# GNSS_RECV.net
KiCad netlist of a schematic drawn in Altium Designer
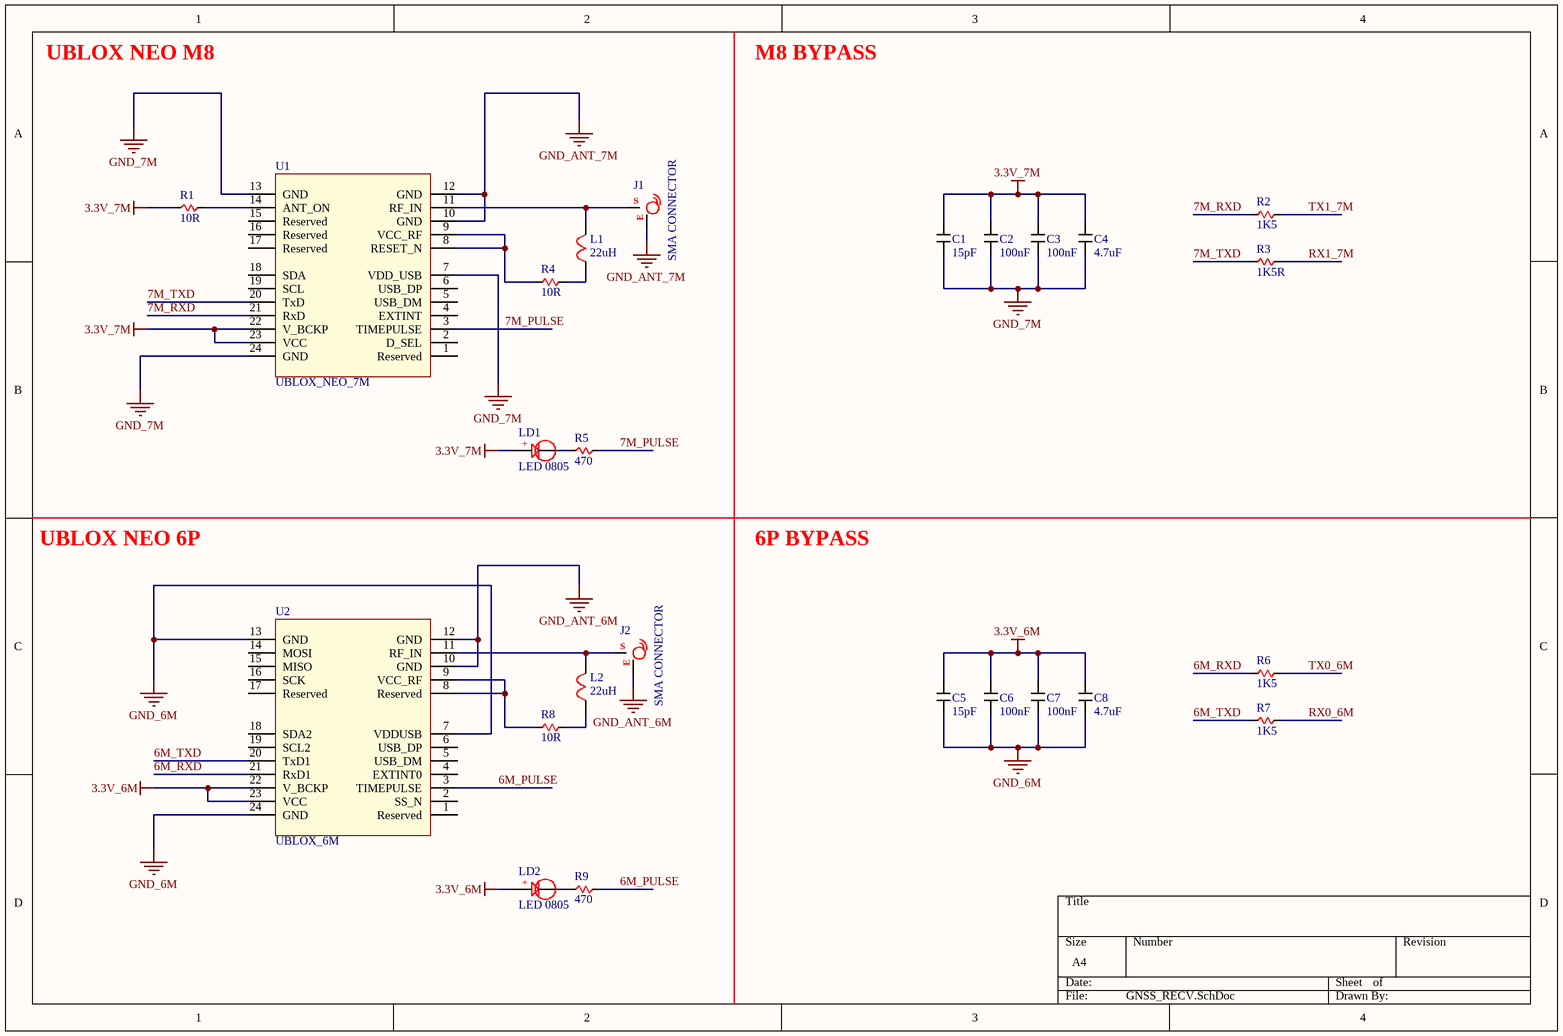
[diagram p0: GNSS_RECV.SchDoc]

(export (version "E")
  (design (tool "Eeschema 10.0.6"))
  (components
    (comp (ref "C1") (value "15pF") (footprint "C 0805") (libsource (lib "SkyWar") (part "C 0805")))
    (comp (ref "C2") (value "100nF") (footprint "C 0805") (libsource (lib "SkyWar") (part "C 0805")))
    (comp (ref "C3") (value "100nF") (footprint "C 0805") (libsource (lib "SkyWar") (part "C 0805")))
    (comp (ref "C4") (value "4.7uF") (footprint "C 0805") (libsource (lib "SkyWar") (part "C 0805")))
    (comp (ref "C5") (value "15pF") (footprint "C 0805") (libsource (lib "SkyWar") (part "C 0805")))
    (comp (ref "C6") (value "100nF") (footprint "C 0805") (libsource (lib "SkyWar") (part "C 0805")))
    (comp (ref "C7") (value "100nF") (footprint "C 0805") (libsource (lib "SkyWar") (part "C 0805")))
    (comp (ref "C8") (value "4.7uF") (footprint "C 0805") (libsource (lib "SkyWar") (part "C 0805")))
    (comp (ref "J1")
      (value "SMA CONNECTOR")
      (footprint "SMA_CONNECTOR")
      (libsource (lib "SkyWar") (part "ANT_SMA"))
    )
    (comp (ref "J2")
      (value "SMA CONNECTOR")
      (footprint "SMA_CONNECTOR")
      (libsource (lib "SkyWar") (part "ANT_SMA"))
    )
    (comp (ref "L1") (value "22uH") (footprint "L 0603") (libsource (lib "SkyWar") (part "L 0603")))
    (comp (ref "L2") (value "22uH") (footprint "L 0603") (libsource (lib "SkyWar") (part "L 0603")))
    (comp (ref "LD1") (value "LED 0805") (footprint "LED 0805") (libsource (lib "SkyWar") (part "LED 0805")))
    (comp (ref "LD2") (value "LED 0805") (footprint "LED 0805") (libsource (lib "SkyWar") (part "LED 0805")))
    (comp (ref "R1") (value "10R") (footprint "R 0805") (libsource (lib "SkyWar") (part "R 0805")))
    (comp (ref "R2") (value "1K5") (footprint "R 0805") (libsource (lib "SkyWar") (part "R 0805")))
    (comp (ref "R3") (value "1K5R") (footprint "R 0805") (libsource (lib "SkyWar") (part "R 0805")))
    (comp (ref "R4") (value "10R") (footprint "R 0805") (libsource (lib "SkyWar") (part "R 0805")))
    (comp (ref "R5") (value "470") (footprint "R 0805") (libsource (lib "SkyWar") (part "R 0805")))
    (comp (ref "R6") (value "1K5") (footprint "R 0805") (libsource (lib "SkyWar") (part "R 0805")))
    (comp (ref "R7") (value "1K5") (footprint "R 0805") (libsource (lib "SkyWar") (part "R 0805")))
    (comp (ref "R8") (value "10R") (footprint "R 0805") (libsource (lib "SkyWar") (part "R 0805")))
    (comp (ref "R9") (value "470") (footprint "R 0805") (libsource (lib "SkyWar") (part "R 0805")))
    (comp (ref "U1")
      (value "UBLOX_NEO_7M")
      (footprint "UBLOX_M8")
      (libsource (lib "SkyWar") (part "UBLOX_M8"))
    )
    (comp (ref "U2")
      (value "UBLOX_6M")
      (footprint "UBLOX_6P")
      (description "UBLOX_NEO_6P")
      (libsource (lib "SkyWar") (part "UBLOX_6P"))
    )
  )
  (nets
    (net (code "1") (name "/6M_PULSE") (class "Default")
      (node (ref "R9") (pin "1") (pinfunction "0_1") (pintype "passive"))
      (node (ref "U2") (pin "3") (pinfunction "TIMEPULSE_3") (pintype "passive"))
    )
    (net (code "2") (name "/6M_RXD") (class "Default")
      (node (ref "R6") (pin "1") (pinfunction "0_1") (pintype "passive"))
      (node (ref "U2") (pin "21") (pinfunction "RxD1_21") (pintype "passive"))
    )
    (net (code "3") (name "/6M_TXD") (class "Default")
      (node (ref "R7") (pin "1") (pinfunction "0_1") (pintype "passive"))
      (node (ref "U2") (pin "20") (pinfunction "TxD1_20") (pintype "passive"))
    )
    (net (code "4") (name "/7M_PULSE") (class "Default")
      (node (ref "R5") (pin "1") (pinfunction "0_1") (pintype "passive"))
      (node (ref "U1") (pin "3") (pinfunction "TIMEPULSE_3") (pintype "passive"))
    )
    (net (code "5") (name "/7M_RXD") (class "Default")
      (node (ref "R2") (pin "1") (pinfunction "0_1") (pintype "passive"))
      (node (ref "U1") (pin "21") (pinfunction "RxD_21") (pintype "passive"))
    )
    (net (code "6") (name "/7M_TXD") (class "Default")
      (node (ref "R3") (pin "1") (pinfunction "0_1") (pintype "passive"))
      (node (ref "U1") (pin "20") (pinfunction "TxD_20") (pintype "passive"))
    )
    (net (code "7") (name "/RX0_6M") (class "Default")
      (node (ref "R7") (pin "2") (pinfunction "1_2") (pintype "passive"))
    )
    (net (code "8") (name "/RX1_7M") (class "Default")
      (node (ref "R3") (pin "2") (pinfunction "1_2") (pintype "passive"))
    )
    (net (code "9") (name "/TX0_6M") (class "Default")
      (node (ref "R6") (pin "2") (pinfunction "1_2") (pintype "passive"))
    )
    (net (code "10") (name "/TX1_7M") (class "Default")
      (node (ref "R2") (pin "2") (pinfunction "1_2") (pintype "passive"))
    )
    (net (code "11") (name "3.3V_6M") (class "Default")
      (node (ref "C5") (pin "2") (pintype "passive"))
      (node (ref "C6") (pin "2") (pintype "passive"))
      (node (ref "C7") (pin "2") (pintype "passive"))
      (node (ref "C8") (pin "2") (pintype "passive"))
      (node (ref "LD2") (pin "1") (pinfunction "3_1") (pintype "passive"))
      (node (ref "U2") (pin "22") (pinfunction "V_BCKP_22") (pintype "passive"))
      (node (ref "U2") (pin "23") (pinfunction "VCC_23") (pintype "passive"))
    )
    (net (code "12") (name "3.3V_7M") (class "Default")
      (node (ref "C1") (pin "2") (pintype "passive"))
      (node (ref "C2") (pin "2") (pintype "passive"))
      (node (ref "C3") (pin "2") (pintype "passive"))
      (node (ref "C4") (pin "2") (pintype "passive"))
      (node (ref "LD1") (pin "1") (pinfunction "3_1") (pintype "passive"))
      (node (ref "R1") (pin "1") (pinfunction "0_1") (pintype "passive"))
      (node (ref "U1") (pin "22") (pinfunction "V_BCKP_22") (pintype "passive"))
      (node (ref "U1") (pin "23") (pinfunction "VCC_23") (pintype "passive"))
    )
    (net (code "13") (name "GND_6M") (class "Default")
      (node (ref "C5") (pin "1") (pintype "passive"))
      (node (ref "C6") (pin "1") (pintype "passive"))
      (node (ref "C7") (pin "1") (pintype "passive"))
      (node (ref "C8") (pin "1") (pintype "passive"))
      (node (ref "U2") (pin "13") (pinfunction "GND_13") (pintype "passive"))
      (node (ref "U2") (pin "24") (pinfunction "GND_24") (pintype "passive"))
      (node (ref "U2") (pin "7") (pinfunction "VDDUSB_7") (pintype "passive"))
    )
    (net (code "14") (name "GND_7M") (class "Default")
      (node (ref "C1") (pin "1") (pintype "passive"))
      (node (ref "C2") (pin "1") (pintype "passive"))
      (node (ref "C3") (pin "1") (pintype "passive"))
      (node (ref "C4") (pin "1") (pintype "passive"))
      (node (ref "U1") (pin "13") (pinfunction "GND_13") (pintype "passive"))
      (node (ref "U1") (pin "24") (pinfunction "GND_24") (pintype "passive"))
      (node (ref "U1") (pin "7") (pinfunction "VDD_USB_7") (pintype "passive"))
    )
    (net (code "15") (name "GND_ANT_6M") (class "Default")
      (node (ref "J2") (pin "2") (pinfunction "2_2") (pintype "passive"))
      (node (ref "U2") (pin "10") (pinfunction "GND_10") (pintype "passive"))
      (node (ref "U2") (pin "12") (pinfunction "GND_12") (pintype "passive"))
    )
    (net (code "16") (name "GND_ANT_7M") (class "Default")
      (node (ref "J1") (pin "2") (pinfunction "2_2") (pintype "passive"))
      (node (ref "U1") (pin "10") (pinfunction "GND_10") (pintype "passive"))
      (node (ref "U1") (pin "12") (pinfunction "GND_12") (pintype "passive"))
    )
    (net (code "17") (name "Net-(J1-S)") (class "Default")
      (node (ref "J1") (pin "1") (pinfunction "S_1") (pintype "passive"))
      (node (ref "L1") (pin "2") (pintype "passive"))
      (node (ref "U1") (pin "11") (pinfunction "RF_IN_11") (pintype "passive"))
    )
    (net (code "18") (name "Net-(J2-S)") (class "Default")
      (node (ref "J2") (pin "1") (pinfunction "S_1") (pintype "passive"))
      (node (ref "L2") (pin "2") (pintype "passive"))
      (node (ref "U2") (pin "11") (pinfunction "RF_IN_11") (pintype "passive"))
    )
    (net (code "19") (name "Net-(LD1-4)") (class "Default")
      (node (ref "LD1") (pin "2") (pinfunction "4_2") (pintype "passive"))
      (node (ref "R5") (pin "2") (pinfunction "1_2") (pintype "passive"))
    )
    (net (code "20") (name "Net-(LD2-4)") (class "Default")
      (node (ref "LD2") (pin "2") (pinfunction "4_2") (pintype "passive"))
      (node (ref "R9") (pin "2") (pinfunction "1_2") (pintype "passive"))
    )
    (net (code "21") (name "Net-(R1-1)") (class "Default")
      (node (ref "R1") (pin "2") (pinfunction "1_2") (pintype "passive"))
      (node (ref "U1") (pin "14") (pinfunction "ANT_ON_14") (pintype "passive"))
    )
    (net (code "22") (name "Net-(R4-0)") (class "Default")
      (node (ref "R4") (pin "1") (pinfunction "0_1") (pintype "passive"))
      (node (ref "U1") (pin "8") (pinfunction "RESET_N_8") (pintype "passive"))
      (node (ref "U1") (pin "9") (pinfunction "VCC_RF_9") (pintype "passive"))
    )
    (net (code "23") (name "Net-(R4-1)") (class "Default")
      (node (ref "L1") (pin "1") (pintype "passive"))
      (node (ref "R4") (pin "2") (pinfunction "1_2") (pintype "passive"))
    )
    (net (code "24") (name "Net-(R8-0)") (class "Default")
      (node (ref "L2") (pin "1") (pintype "passive"))
      (node (ref "R8") (pin "1") (pinfunction "0_1") (pintype "passive"))
    )
    (net (code "25") (name "Net-(R8-1)") (class "Default")
      (node (ref "R8") (pin "2") (pinfunction "1_2") (pintype "passive"))
      (node (ref "U2") (pin "8") (pinfunction "Reserved_8") (pintype "passive"))
      (node (ref "U2") (pin "9") (pinfunction "VCC_RF_9") (pintype "passive"))
    )
    (net (code "26") (name "unconnected-(U1-D_SEL-Pad2)") (class "Default")
      (node (ref "U1") (pin "2") (pinfunction "D_SEL_2") (pintype "passive"))
    )
    (net (code "27") (name "unconnected-(U1-EXTINT-Pad4)") (class "Default")
      (node (ref "U1") (pin "4") (pinfunction "EXTINT_4") (pintype "passive"))
    )
    (net (code "28") (name "unconnected-(U1-Reserved-Pad1)") (class "Default")
      (node (ref "U1") (pin "1") (pinfunction "Reserved_1") (pintype "passive"))
    )
    (net (code "29") (name "unconnected-(U1-Reserved-Pad15)") (class "Default")
      (node (ref "U1") (pin "15") (pinfunction "Reserved_15") (pintype "passive"))
    )
    (net (code "30") (name "unconnected-(U1-Reserved-Pad16)") (class "Default")
      (node (ref "U1") (pin "16") (pinfunction "Reserved_16") (pintype "passive"))
    )
    (net (code "31") (name "unconnected-(U1-Reserved-Pad17)") (class "Default")
      (node (ref "U1") (pin "17") (pinfunction "Reserved_17") (pintype "passive"))
    )
    (net (code "32") (name "unconnected-(U1-SCL-Pad19)") (class "Default")
      (node (ref "U1") (pin "19") (pinfunction "SCL_19") (pintype "passive"))
    )
    (net (code "33") (name "unconnected-(U1-SDA-Pad18)") (class "Default")
      (node (ref "U1") (pin "18") (pinfunction "SDA_18") (pintype "passive"))
    )
    (net (code "34") (name "unconnected-(U1-USB_DM-Pad5)") (class "Default")
      (node (ref "U1") (pin "5") (pinfunction "USB_DM_5") (pintype "passive"))
    )
    (net (code "35") (name "unconnected-(U1-USB_DP-Pad6)") (class "Default")
      (node (ref "U1") (pin "6") (pinfunction "USB_DP_6") (pintype "passive"))
    )
    (net (code "36") (name "unconnected-(U2-EXTINT0-Pad4)") (class "Default")
      (node (ref "U2") (pin "4") (pinfunction "EXTINT0_4") (pintype "passive"))
    )
    (net (code "37") (name "unconnected-(U2-MISO-Pad15)") (class "Default")
      (node (ref "U2") (pin "15") (pinfunction "MISO_15") (pintype "passive"))
    )
    (net (code "38") (name "unconnected-(U2-MOSI-Pad14)") (class "Default")
      (node (ref "U2") (pin "14") (pinfunction "MOSI_14") (pintype "passive"))
    )
    (net (code "39") (name "unconnected-(U2-Reserved-Pad1)") (class "Default")
      (node (ref "U2") (pin "1") (pinfunction "Reserved_1") (pintype "passive"))
    )
    (net (code "40") (name "unconnected-(U2-Reserved-Pad17)") (class "Default")
      (node (ref "U2") (pin "17") (pinfunction "Reserved_17") (pintype "passive"))
    )
    (net (code "41") (name "unconnected-(U2-SCK-Pad16)") (class "Default")
      (node (ref "U2") (pin "16") (pinfunction "SCK_16") (pintype "passive"))
    )
    (net (code "42") (name "unconnected-(U2-SCL2-Pad19)") (class "Default")
      (node (ref "U2") (pin "19") (pinfunction "SCL2_19") (pintype "passive"))
    )
    (net (code "43") (name "unconnected-(U2-SDA2-Pad18)") (class "Default")
      (node (ref "U2") (pin "18") (pinfunction "SDA2_18") (pintype "passive"))
    )
    (net (code "44") (name "unconnected-(U2-SS_N-Pad2)") (class "Default")
      (node (ref "U2") (pin "2") (pinfunction "SS_N_2") (pintype "passive"))
    )
    (net (code "45") (name "unconnected-(U2-USB_DM-Pad5)") (class "Default")
      (node (ref "U2") (pin "5") (pinfunction "USB_DM_5") (pintype "passive"))
    )
    (net (code "46") (name "unconnected-(U2-USB_DP-Pad6)") (class "Default")
      (node (ref "U2") (pin "6") (pinfunction "USB_DP_6") (pintype "passive"))
    )
  )
)
